# 02_Boost_Converter.net
KiCad netlist of a schematic drawn in Altium Designer
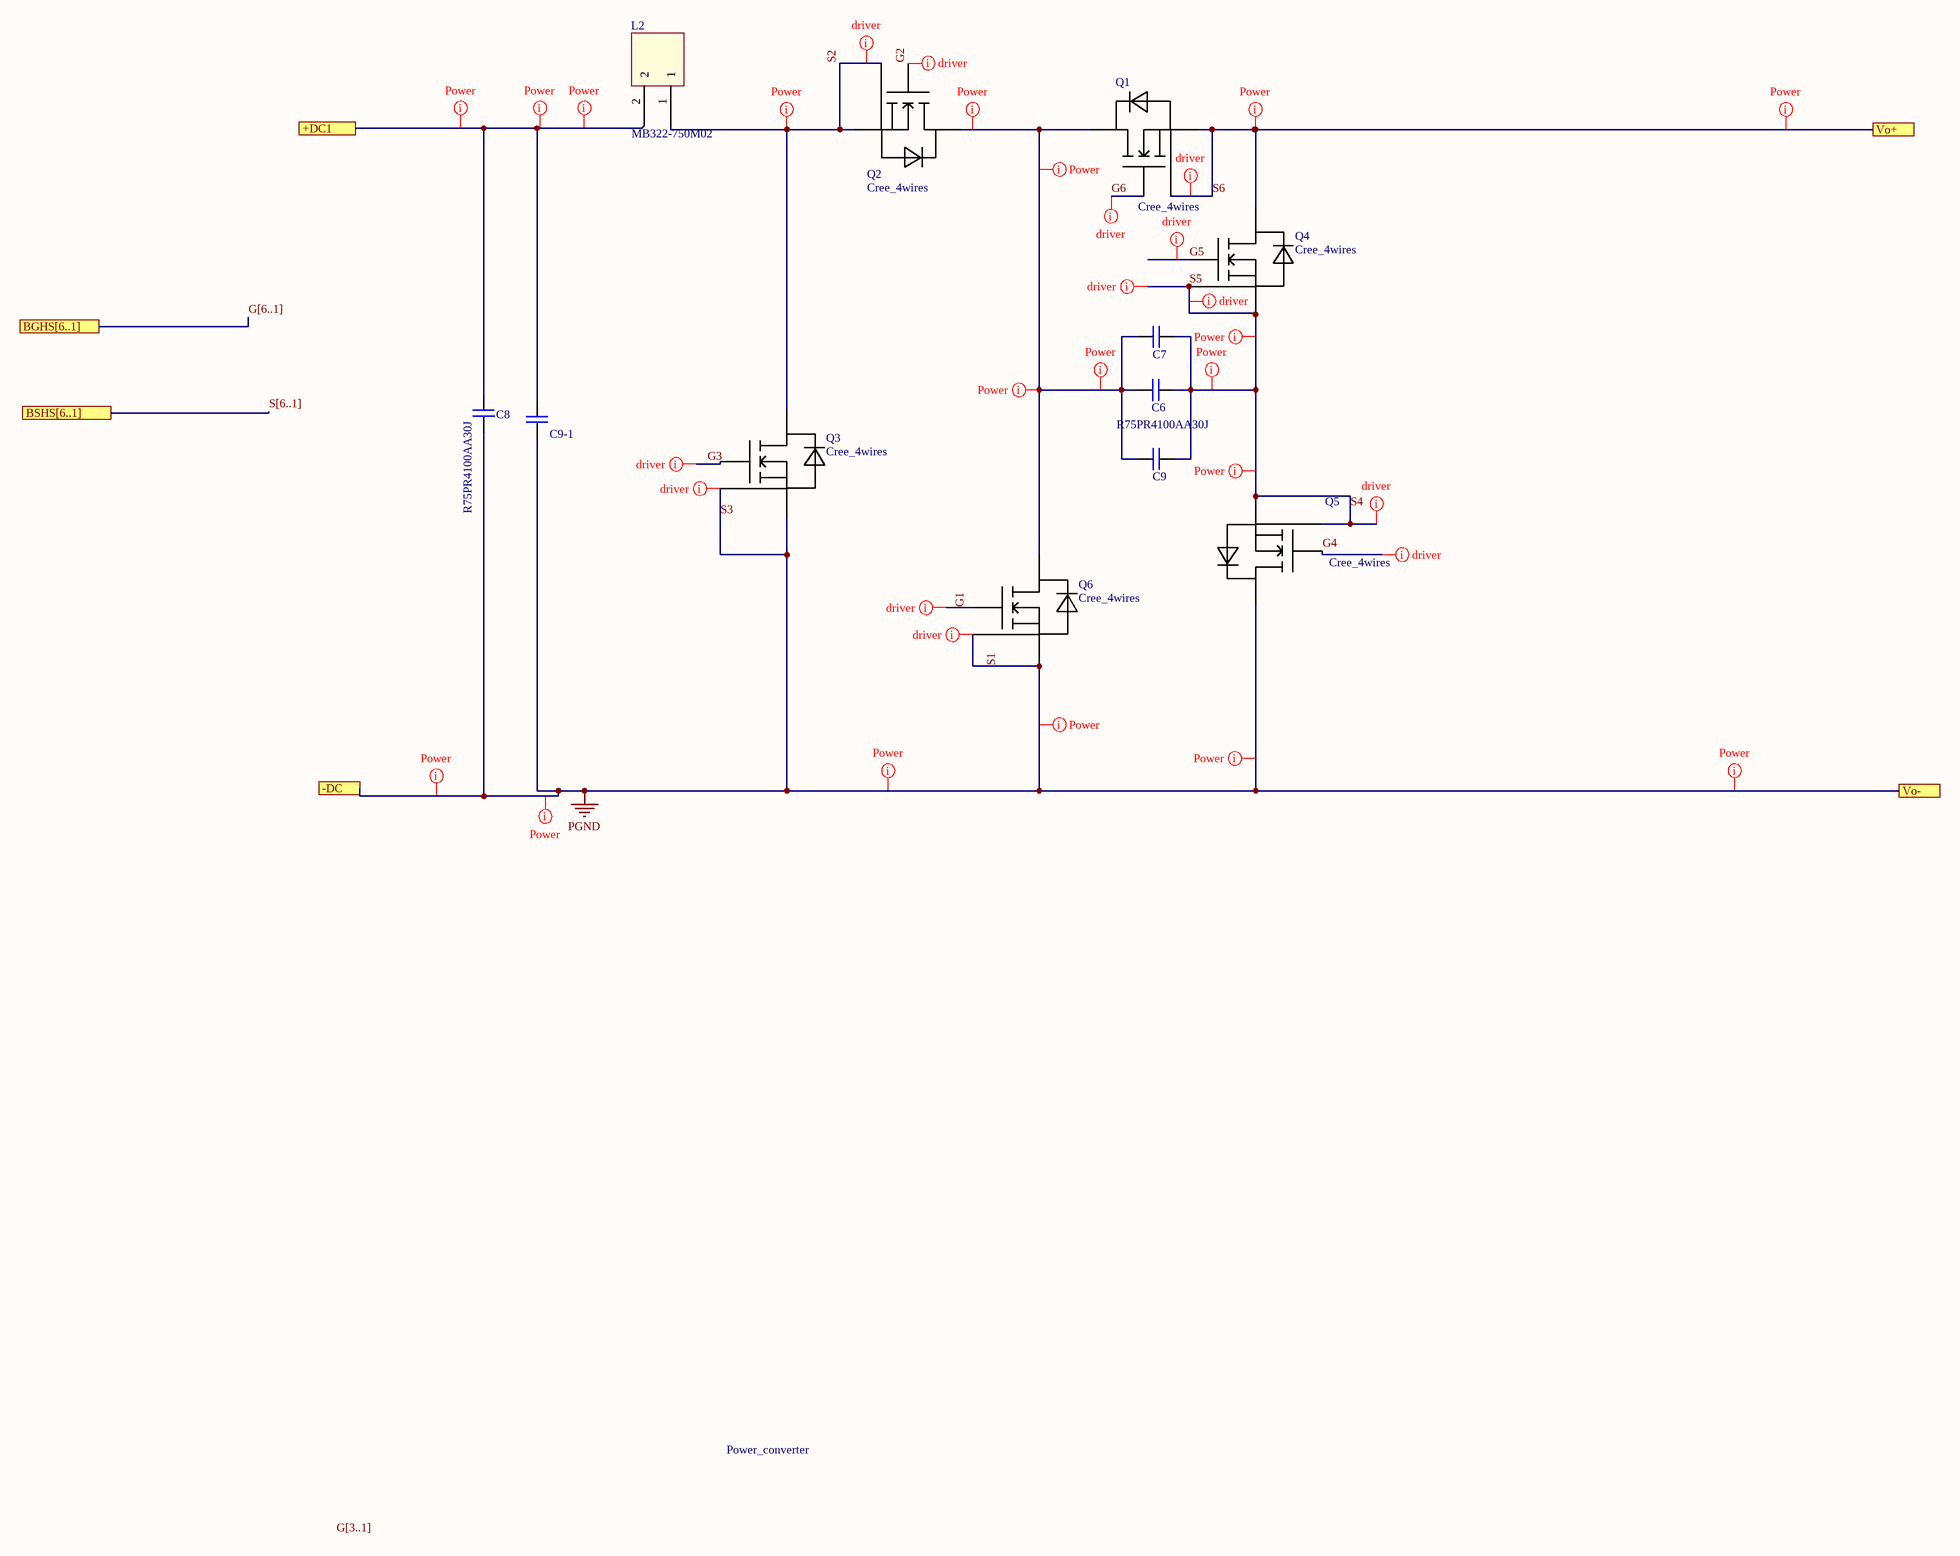
[diagram p0: 02_Boost_Converter.SchDoc]

(export (version "E")
  (design (tool "Eeschema 10.0.6"))
  (components
    (comp (ref "C6")
      (value "R75PR4100AA30J")
      (footprint "CAP_6")
      (libsource (lib "NEW_VERSION") (part "C_ceram_HV"))
    )
    (comp (ref "C7") (value "C_ceram_HV") (footprint "CAP_250V") (libsource (lib "") (part "C_ceram_HV_1")))
    (comp (ref "C8")
      (value "R75PR4100AA30J")
      (footprint "32x22")
      (libsource (lib "capacitors") (part "R75PR4100AA30J"))
    )
    (comp (ref "C9") (value "C_ceram_HV") (footprint "CAP_250V") (libsource (lib "") (part "C_ceram_HV_1")))
    (comp (ref "C9-1")
      (value "C_ceram_HV")
      (footprint "C_ceram_HV")
      (libsource (lib "") (part "C_ceram_HV_2"))
    )
    (comp (ref "L2")
      (value "MB322-750M02")
      (footprint "2_HOLES_7.5")
      (libsource (lib "Library") (part "MB322-750M02"))
    )
    (comp (ref "Q1")
      (value "Cree_4wires")
      (footprint "VT4_SicMosfet")
      (libsource (lib "NEW_VERSION") (part "Cree_4wires"))
    )
    (comp (ref "Q2")
      (value "Cree_4wires")
      (footprint "VT4_SicMosfet")
      (libsource (lib "NEW_VERSION") (part "Cree_4wires"))
    )
    (comp (ref "Q3")
      (value "Cree_4wires")
      (footprint "VT4_SicMosfet")
      (libsource (lib "NEW_VERSION") (part "Cree_4wires"))
    )
    (comp (ref "Q4")
      (value "Cree_4wires")
      (footprint "VT4_SicMosfet")
      (libsource (lib "NEW_VERSION") (part "Cree_4wires"))
    )
    (comp (ref "Q5")
      (value "Cree_4wires")
      (footprint "VT4_SicMosfet")
      (libsource (lib "NEW_VERSION") (part "Cree_4wires"))
    )
    (comp (ref "Q6")
      (value "Cree_4wires")
      (footprint "VT4_SicMosfet")
      (libsource (lib "NEW_VERSION") (part "Cree_4wires"))
    )
  )
  (nets
    (net (code "1") (name "/+DC1") (class "Default")
      (node (ref "C8") (pin "1") (pinfunction "1_1") (pintype "passive"))
      (node (ref "C9-1") (pin "1") (pinfunction "1_1") (pintype "passive"))
      (node (ref "L2") (pin "2") (pinfunction "2_2") (pintype "passive"))
    )
    (net (code "2") (name "/G1") (class "Default")
      (node (ref "Q6") (pin "4") (pinfunction "G_4") (pintype "passive"))
    )
    (net (code "3") (name "/G2") (class "Default")
      (node (ref "Q2") (pin "4") (pinfunction "G_4") (pintype "passive"))
    )
    (net (code "4") (name "/G3") (class "Default")
      (node (ref "Q3") (pin "4") (pinfunction "G_4") (pintype "passive"))
    )
    (net (code "5") (name "/G4") (class "Default")
      (node (ref "Q5") (pin "4") (pinfunction "G_4") (pintype "passive"))
    )
    (net (code "6") (name "/G5") (class "Default")
      (node (ref "Q4") (pin "4") (pinfunction "G_4") (pintype "passive"))
    )
    (net (code "7") (name "/G6") (class "Default")
      (node (ref "Q1") (pin "4") (pinfunction "G_4") (pintype "passive"))
    )
    (net (code "10") (name "/S2") (class "Default")
      (node (ref "L2") (pin "1") (pinfunction "1_1") (pintype "passive"))
      (node (ref "Q2") (pin "2") (pinfunction "S_2") (pintype "passive"))
      (node (ref "Q2") (pin "3") (pinfunction "SG_3") (pintype "passive"))
      (node (ref "Q3") (pin "1") (pinfunction "D_1") (pintype "passive"))
    )
    (net (code "11") (name "/S5") (class "Default")
      (node (ref "C6") (pin "2") (pinfunction "2_2") (pintype "passive"))
      (node (ref "C7") (pin "2") (pinfunction "2_2") (pintype "passive"))
      (node (ref "C9") (pin "2") (pinfunction "2_2") (pintype "passive"))
      (node (ref "Q4") (pin "2") (pinfunction "S_2") (pintype "passive"))
      (node (ref "Q4") (pin "3") (pinfunction "SG_3") (pintype "passive"))
      (node (ref "Q5") (pin "2") (pinfunction "S_2") (pintype "passive"))
      (node (ref "Q5") (pin "3") (pinfunction "SG_3") (pintype "passive"))
    )
    (net (code "12") (name "/S6") (class "Default")
      (node (ref "Q1") (pin "2") (pinfunction "S_2") (pintype "passive"))
      (node (ref "Q1") (pin "3") (pinfunction "SG_3") (pintype "passive"))
      (node (ref "Q4") (pin "1") (pinfunction "D_1") (pintype "passive"))
    )
    (net (code "14") (name "Net-(Q1-D)") (class "Default")
      (node (ref "C6") (pin "1") (pinfunction "1_1") (pintype "passive"))
      (node (ref "C7") (pin "1") (pinfunction "1_1") (pintype "passive"))
      (node (ref "C9") (pin "1") (pinfunction "1_1") (pintype "passive"))
      (node (ref "Q1") (pin "1") (pinfunction "D_1") (pintype "passive"))
      (node (ref "Q2") (pin "1") (pinfunction "D_1") (pintype "passive"))
      (node (ref "Q6") (pin "1") (pinfunction "D_1") (pintype "passive"))
    )
    (net (code "15") (name "PGND") (class "Default")
      (node (ref "C8") (pin "2") (pinfunction "2_2") (pintype "passive"))
      (node (ref "C9-1") (pin "2") (pinfunction "2_2") (pintype "passive"))
      (node (ref "Q3") (pin "2") (pinfunction "S_2") (pintype "passive"))
      (node (ref "Q3") (pin "3") (pinfunction "SG_3") (pintype "passive"))
      (node (ref "Q5") (pin "1") (pinfunction "D_1") (pintype "passive"))
      (node (ref "Q6") (pin "2") (pinfunction "S_2") (pintype "passive"))
      (node (ref "Q6") (pin "3") (pinfunction "SG_3") (pintype "passive"))
    )
  )
)
